# EzRing.net
KiCad netlist of a schematic drawn in Altium Designer
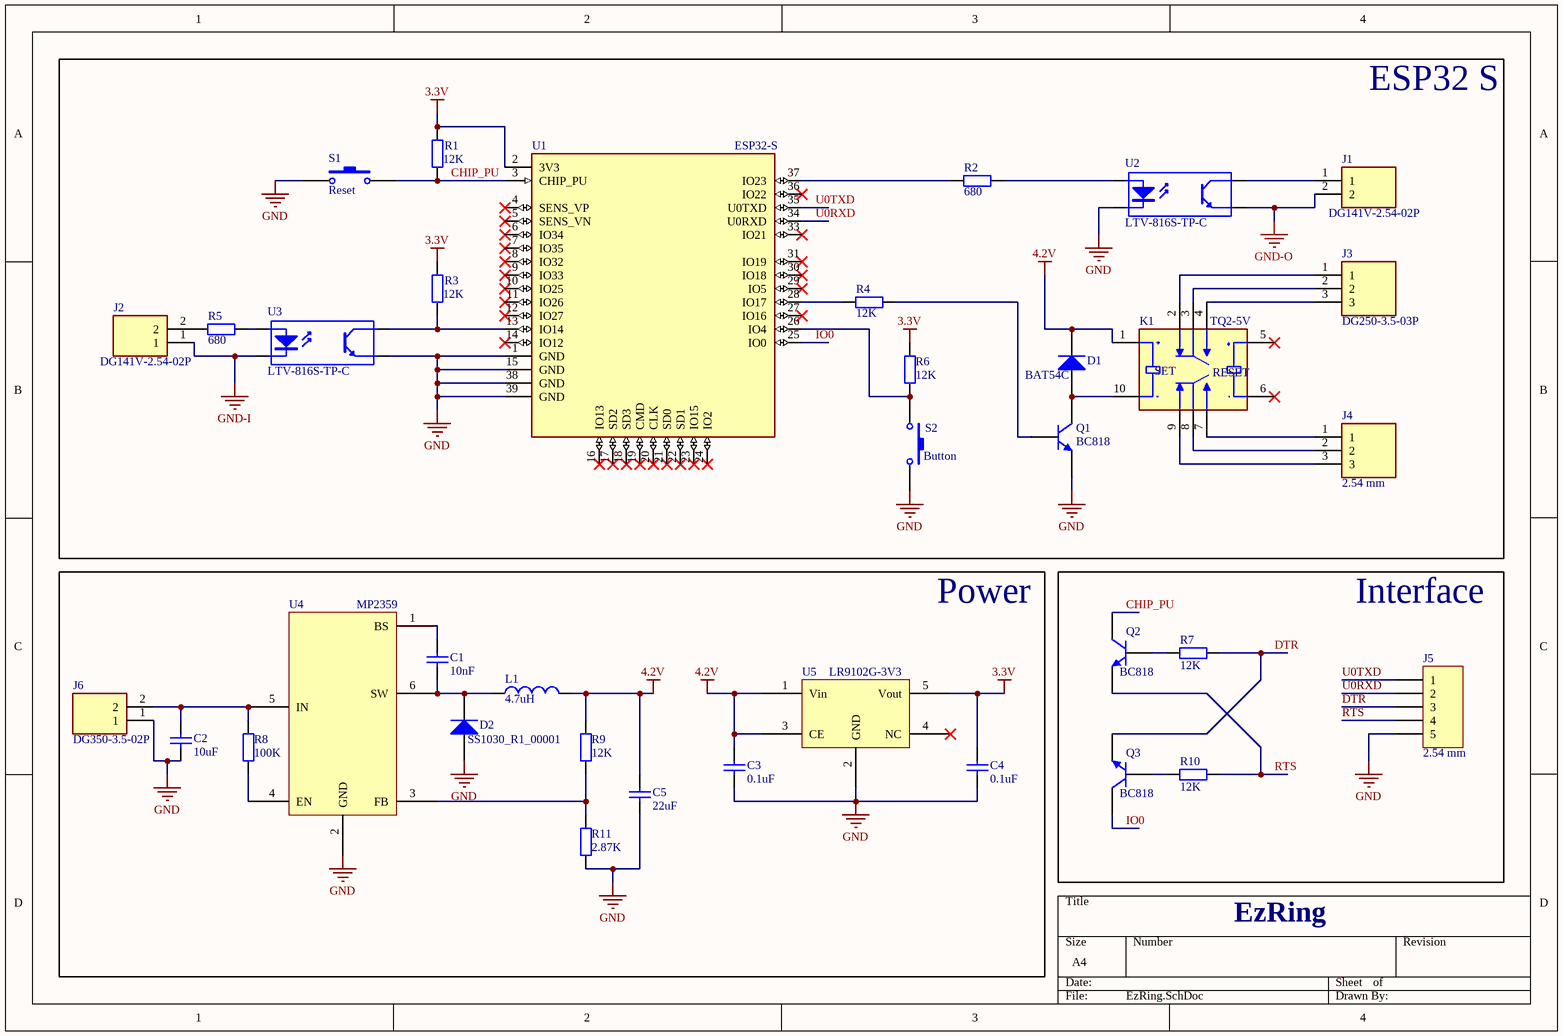
[diagram p0: EzRing.SchDoc]

(export (version "E")
  (design (tool "Eeschema 10.0.6"))
  (components
    (comp (ref "C1")
      (value "10nF")
      (footprint "0805")
      (description "MLCC (2012) 0805 10nF 100VDC ±10% X7R")
      (fields (field (name "OZDISAN PART#") "CL21B103KCANNNC") (field (name "PUBLISHER") "Altium Limited"))
      (libsource (lib "Miscellaneous Devices") (part "Cap"))
    )
    (comp (ref "C2")
      (value "10uF")
      (footprint "0805")
      (description "MLCC (2012) 0805 10uF 25VDC ±10% X5R")
      (fields (field (name "OZDISAN PART#") "CL21A106KAYNNNE") (field (name "PUBLISHER") "Altium Limited"))
      (libsource (lib "Miscellaneous Devices") (part "Cap"))
    )
    (comp (ref "C3")
      (value "0.1uF")
      (footprint "0805")
      (description "Capacitor")
      (fields (field (name "OZDISAN PART#") "CL21A226MAQNNNE") (field (name "PUBLISHER") "Altium Limited"))
      (libsource (lib "Miscellaneous Devices") (part "Cap"))
    )
    (comp (ref "C4")
      (value "0.1uF")
      (footprint "0805")
      (description "Capacitor")
      (fields (field (name "OZDISAN PART#") "CL21A226MAQNNNE") (field (name "PUBLISHER") "Altium Limited"))
      (libsource (lib "Miscellaneous Devices") (part "Cap"))
    )
    (comp (ref "C5")
      (value "22uF")
      (footprint "0805")
      (description "MLCC (2012) 0805 22uF 6.3VDC ±20% X5R")
      (fields (field (name "OZDISAN PART#") "CL21A226MQQNNNE") (field (name "PUBLISHER") "Altium Limited"))
      (libsource (lib "Miscellaneous Devices") (part "Cap"))
    )
    (comp (ref "D1")
      (value "BAT54C")
      (footprint "BAT54 series")
      (description "DIODE SCHOTTKY 2*0.2A 30V SOT23 CATHODE PHILIPS")
      (fields (field (name "OZDISAN PART#") "BAT54C,215") (field (name "PUBLISHER") "Altium Limited"))
      (libsource (lib "Miscellaneous Devices") (part "Diode"))
    )
    (comp (ref "D2")
      (value "SS1030_R1_00001")
      (footprint "SOD123 DIODE")
      (description "DIODE SCHOTTKY 1A 30V SOD123 SMT")
      (fields (field (name "PUBLISHER") "Altium Limited"))
      (libsource (lib "Miscellaneous Devices") (part "Diode"))
    )
    (comp (ref "J1")
      (value "DG141V-2.54-02P")
      (footprint "term blk 2p 2.54 2 leg 5.08 between legs")
      (fields
        (field (name "MP") "282843-2")
        (field (name "MF") "{'manufacturer': 'TE Connectivity'}")
        (field (name "OZDISAN PART#") "DG141V-2.54-02P-14-00AH")
      )
      (libsource (lib "MT-Sources") (part "282843-2"))
    )
    (comp (ref "J2")
      (value "DG141V-2.54-02P")
      (footprint "term blk 2p 2.54 2 leg 5.08 between legs")
      (fields
        (field (name "MP") "282843-2")
        (field (name "MF") "{'manufacturer': 'TE Connectivity'}")
        (field (name "OZDISAN PART#") "DG141V-2.54-02P-14-00AH")
      )
      (libsource (lib "") (part "282843-2_1"))
    )
    (comp (ref "J3")
      (value "DG250-3.5-03P")
      (footprint "term blk 2.54 3p 2 leg 5.08  between leg")
      (description "TERM.BLK.3.50MM 3P PCB TYPE GRAY GAOSONG")
      (fields (field (name "MF") "TE Connectivity") (field (name "DIGI-KEY_PART_NUMBER") "A98085-ND"))
      (libsource (lib "MT-Sources") (part "282843-3"))
    )
    (comp (ref "J4")
      (value "2.54 mm")
      (footprint "HEADER-2.54-03")
      (description "TERMI-BLOCK PCB HEADER 2.54")
      (fields (field (name "MF") "TE Connectivity") (field (name "DIGI-KEY_PART_NUMBER") "A98085-ND"))
      (libsource (lib "MT-Sources") (part "282843-3"))
    )
    (comp (ref "J5")
      (value "2.54 mm")
      (footprint "HEADER-2.54-5P")
      (description "Header, 5-Pin boşta kalacak.")
      (fields (field (name "PUBLISHER") "Altium Limited"))
      (libsource (lib "Miscellaneous Connectors") (part "Header 5"))
    )
    (comp (ref "J6")
      (value "DG350-3.5-02P")
      (footprint "Header-3.5-02")
      (description "TERM.BLK.3.81MM 2P PCB TYPE GREEN GAOSONG")
      (fields (field (name "MP") "282843-2") (field (name "MF") "{'manufacturer': 'TE Connectivity'}"))
      (libsource (lib "") (part "282843-2_1"))
    )
    (comp (ref "K1")
      (value "TQ2-5V")
      (footprint "RELAY_TQ2_2C_PAN")
      (description "RELAY 1A 5VDC TELECOM TYPE PANASONIC")
      (fields (field (name "MP") "EE2-3TNUH-L") (field (name "MF") "KEMET"))
      (libsource (lib "MT-Sources") (part "EE2-3TNUH-L"))
    )
    (comp (ref "L1")
      (value "4.7uH")
      (footprint "INDC2012X10N")
      (description "INDUCTOR FIXED 0805 4.7UH SMD")
      (fields (field (name "OZDISAN PART#") "CL2012C-4R7M-N") (field (name "PUBLISHER") "Altium Limited"))
      (libsource (lib "Miscellaneous Devices") (part "Inductor"))
    )
    (comp (ref "Q1")
      (value "BC818")
      (footprint "BC818")
      (description "BC818-16W,115 - TRANSISTOR DIS.500mA 25V NPN SOT323 GEN. SMT")
      (fields (field (name "OZDISAN PART#") "BC818-16W,115") (field (name "PUBLISHER") "Altium Limited"))
      (libsource (lib "Miscellaneous Devices") (part "NPN"))
    )
    (comp (ref "Q2")
      (value "BC818")
      (footprint "BC818")
      (description "BC818-16W,115 - TRANSISTOR DIS.500mA 25V NPN SOT323 GEN. SMT")
      (fields (field (name "OZDISAN PART#") "BC818-16W,115") (field (name "PUBLISHER") "Altium Limited"))
      (libsource (lib "Miscellaneous Devices") (part "NPN"))
    )
    (comp (ref "Q3")
      (value "BC818")
      (footprint "BC818")
      (description "BC818-16W,115 - TRANSISTOR DIS.500mA 25V NPN SOT323 GEN. SMT")
      (fields (field (name "OZDISAN PART#") "BC818-16W,115") (field (name "PUBLISHER") "Altium Limited"))
      (libsource (lib "Miscellaneous Devices") (part "NPN"))
    )
    (comp (ref "R1")
      (value "12K")
      (footprint "0805")
      (description "Resistor")
      (fields (field (name "OZDISAN PART#") "0805S8J0123T5E") (field (name "PUBLISHER") "Altium Limited"))
      (libsource (lib "") (part "Res2_2"))
    )
    (comp (ref "R2")
      (value "680")
      (footprint "0805")
      (description "Resistor")
      (fields (field (name "OZDISAN PART#") "0805S8J0681T5E") (field (name "PUBLISHER") "Altium Limited"))
      (libsource (lib "Miscellaneous Devices") (part "Res2"))
    )
    (comp (ref "R3")
      (value "12K")
      (footprint "0805")
      (description "Resistor")
      (fields (field (name "OZDISAN PART#") "0805S8J0123T5E") (field (name "PUBLISHER") "Altium Limited"))
      (libsource (lib "") (part "Res2_2"))
    )
    (comp (ref "R4")
      (value "12K")
      (footprint "0805")
      (description "Resistor")
      (fields (field (name "OZDISAN PART#") "0805S8J0123T5E") (field (name "PUBLISHER") "Altium Limited"))
      (libsource (lib "") (part "Res2_3"))
    )
    (comp (ref "R5")
      (value "680")
      (footprint "AXIAL-0.4")
      (description "Dip Resistor")
      (fields (field (name "OZDISAN PART#") "MF01WJJ0681A10") (field (name "PUBLISHER") "Altium Limited"))
      (libsource (lib "Miscellaneous Devices") (part "Res2"))
    )
    (comp (ref "R6")
      (value "12K")
      (footprint "0805")
      (description "Resistor")
      (fields (field (name "OZDISAN PART#") "0805S8J0123T5E") (field (name "PUBLISHER") "Altium Limited"))
      (libsource (lib "") (part "Res2_1"))
    )
    (comp (ref "R7")
      (value "12K")
      (footprint "0805")
      (description "Resistor")
      (fields (field (name "OZDISAN PART#") "0805S8J0123T5E") (field (name "PUBLISHER") "Altium Limited"))
      (libsource (lib "Miscellaneous Devices") (part "Res2"))
    )
    (comp (ref "R8")
      (value "100K")
      (footprint "0805")
      (description "Resistor")
      (fields (field (name "OZDISAN PART#") "0805S8J0104T5E") (field (name "PUBLISHER") "Altium Limited"))
      (libsource (lib "") (part "Res2_1"))
    )
    (comp (ref "R9")
      (value "12K")
      (footprint "0805")
      (description "Resistor")
      (fields (field (name "OZDISAN PART#") "0805S8J0123T5E") (field (name "PUBLISHER") "Altium Limited"))
      (libsource (lib "") (part "Res2_1"))
    )
    (comp (ref "R10")
      (value "12K")
      (footprint "0805")
      (description "Resistor")
      (fields (field (name "OZDISAN PART#") "0805S8J0123T5E") (field (name "PUBLISHER") "Altium Limited"))
      (libsource (lib "Miscellaneous Devices") (part "Res2"))
    )
    (comp (ref "R11")
      (value "2.87K")
      (footprint "0805")
      (description "Resistor")
      (fields (field (name "OZDISAN PART#") "0805S8F2871T5E") (field (name "PUBLISHER") "Altium Limited"))
      (libsource (lib "") (part "Res2_1"))
    )
    (comp (ref "S1")
      (value "Reset")
      (footprint "Kısa Devre anahtarlaması")
      (description "Burayı bir cımbız ile kısa devre yapılabilecek bir yapıda bırakacağız. buton koyulmayacak.")
      (fields (field (name "PUBLISHER") "Altium Limited"))
      (libsource (lib "Miscellaneous Devices") (part "SW-PB"))
    )
    (comp (ref "S2")
      (value "Button")
      (footprint "Push Button")
      (description "PUSH")
      (fields
        (field (name "OZDISAN PART#") "L-KLS7-TS6604-4.3-160-T")
        (field (name "PUBLISHER") "Altium Limited")
      )
      (libsource (lib "Miscellaneous Devices") (part "SW-PB"))
    )
    (comp (ref "U1")
      (value "ESP32-S")
      (footprint "ESP-32S")
      (fields (field (name "OZDISAN PART#") "ESP32-S (32MBIT)"))
      (libsource (lib "MT-Sources") (part "ESP32-S"))
    )
    (comp (ref "U2")
      (value "LTV-816S-TP-C")
      (footprint "OPTO LTV-816S")
      (description "IC-816 OPTO SMD")
      (fields (field (name "PUBLISHER") "Altium Limited"))
      (libsource (lib "Miscellaneous Devices") (part "Optoisolator1"))
    )
    (comp (ref "U3")
      (value "LTV-816S-TP-C")
      (footprint "OPTO LTV-816S")
      (description "IC-816 OPTO SMD")
      (fields (field (name "PUBLISHER") "Altium Limited"))
      (libsource (lib "Miscellaneous Devices") (part "Optoisolator1"))
    )
    (comp (ref "U4")
      (value "MP2359")
      (footprint "MP2359 vol reg TSOT23-6")
      (description "IC-2359 V.REG BUCK ADJ 1.2A TSOT23-6")
      (fields (field (name "OZDISAN PART#") "MP2359DJ-LF-Z"))
      (libsource (lib "MT-Sources") (part "MP2359"))
    )
    (comp (ref "U5")
      (value "LR9102G-3V3")
      (footprint "LR9102G-3V3-AE5-R")
      (description "IC-LR9102 V.REG 3V3 SOT-23-5 TR UTC (0-6,6V to 3,3V)")
      (fields (field (name "OZDISAN PART#") "LR9102G-3V3-AE5-R"))
      (libsource (lib "MT-Sources") (part "LR9102G-3V3"))
    )
  )
  (nets
    (net (code "1") (name "3.3V") (class "Default")
      (node (ref "C4") (pin "2") (pinfunction "2_2") (pintype "passive"))
      (node (ref "R1") (pin "1") (pinfunction "1_1") (pintype "passive"))
      (node (ref "R3") (pin "1") (pinfunction "1_1") (pintype "passive"))
      (node (ref "R6") (pin "2") (pinfunction "2_2") (pintype "passive"))
      (node (ref "U1") (pin "2") (pinfunction "3V3_2") (pintype "power_in"))
      (node (ref "U5") (pin "5") (pinfunction "Vout_5") (pintype "passive"))
    )
    (net (code "2") (name "4.2V") (class "Default")
      (node (ref "C3") (pin "2") (pinfunction "2_2") (pintype "passive"))
      (node (ref "C5") (pin "2") (pinfunction "2_2") (pintype "passive"))
      (node (ref "D1") (pin "2") (pinfunction "K_2") (pintype "passive"))
      (node (ref "K1") (pin "1") (pinfunction "1_1") (pintype "passive"))
      (node (ref "L1") (pin "2") (pinfunction "2_2") (pintype "passive"))
      (node (ref "R9") (pin "2") (pinfunction "2_2") (pintype "passive"))
      (node (ref "U5") (pin "1") (pinfunction "Vin_1") (pintype "passive"))
      (node (ref "U5") (pin "3") (pinfunction "CE_3") (pintype "passive"))
    )
    (net (code "3") (name "GND") (class "Default")
      (node (ref "C2") (pin "1") (pinfunction "1_1") (pintype "passive"))
      (node (ref "C3") (pin "1") (pinfunction "1_1") (pintype "passive"))
      (node (ref "C4") (pin "1") (pinfunction "1_1") (pintype "passive"))
      (node (ref "C5") (pin "1") (pinfunction "1_1") (pintype "passive"))
      (node (ref "D2") (pin "1") (pinfunction "A_1") (pintype "passive"))
      (node (ref "J5") (pin "5") (pinfunction "5_5") (pintype "passive"))
      (node (ref "J6") (pin "1") (pinfunction "1_1") (pintype "passive"))
      (node (ref "Q1") (pin "3") (pinfunction "E_3") (pintype "passive"))
      (node (ref "R11") (pin "1") (pinfunction "1_1") (pintype "passive"))
      (node (ref "S1") (pin "1") (pinfunction "1_1") (pintype "passive"))
      (node (ref "S2") (pin "2") (pinfunction "2_2") (pintype "passive"))
      (node (ref "U1") (pin "1") (pinfunction "GND_1") (pintype "power_in"))
      (node (ref "U1") (pin "15") (pinfunction "GND_15") (pintype "power_in"))
      (node (ref "U1") (pin "38") (pinfunction "GND_38") (pintype "power_in"))
      (node (ref "U1") (pin "39") (pinfunction "GND_39") (pintype "power_in"))
      (node (ref "U2") (pin "2") (pinfunction "K_2") (pintype "passive"))
      (node (ref "U3") (pin "3") (pinfunction "E_3") (pintype "passive"))
      (node (ref "U4") (pin "2") (pinfunction "GND_2") (pintype "passive"))
      (node (ref "U5") (pin "2") (pinfunction "GND_2") (pintype "passive"))
    )
    (net (code "4") (name "GND-I") (class "Default")
      (node (ref "J2") (pin "1") (pinfunction "1_1") (pintype "passive"))
      (node (ref "U3") (pin "2") (pinfunction "K_2") (pintype "passive"))
    )
    (net (code "5") (name "GND-O") (class "Default")
      (node (ref "J1") (pin "2") (pinfunction "2_2") (pintype "passive"))
      (node (ref "U2") (pin "3") (pinfunction "E_3") (pintype "passive"))
    )
    (net (code "6") (name "Net-(D1-A)") (class "Default")
      (node (ref "D1") (pin "1") (pinfunction "A_1") (pintype "passive"))
      (node (ref "K1") (pin "10") (pinfunction "10_10") (pintype "passive"))
      (node (ref "Q1") (pin "1") (pinfunction "C_1") (pintype "passive"))
    )
    (net (code "7") (name "Net-(D2-K)") (class "Default")
      (node (ref "C1") (pin "1") (pinfunction "1_1") (pintype "passive"))
      (node (ref "D2") (pin "2") (pinfunction "K_2") (pintype "passive"))
      (node (ref "L1") (pin "1") (pinfunction "1_1") (pintype "passive"))
      (node (ref "U4") (pin "6") (pinfunction "SW_6") (pintype "passive"))
    )
    (net (code "8") (name "Net-(J2-Pad2)") (class "Default")
      (node (ref "J2") (pin "2") (pinfunction "2_2") (pintype "passive"))
      (node (ref "R5") (pin "1") (pinfunction "1_1") (pintype "passive"))
    )
    (net (code "9") (name "Net-(J3-Pad1)") (class "Default")
      (node (ref "J3") (pin "1") (pinfunction "1_1") (pintype "passive"))
      (node (ref "K1") (pin "2") (pinfunction "2_2") (pintype "passive"))
    )
    (net (code "10") (name "Net-(J3-Pad2)") (class "Default")
      (node (ref "J3") (pin "2") (pinfunction "2_2") (pintype "passive"))
      (node (ref "K1") (pin "3") (pinfunction "3_3") (pintype "passive"))
    )
    (net (code "11") (name "Net-(J3-Pad3)") (class "Default")
      (node (ref "J3") (pin "3") (pinfunction "3_3") (pintype "passive"))
      (node (ref "K1") (pin "4") (pinfunction "4_4") (pintype "passive"))
    )
    (net (code "12") (name "Net-(J4-Pad1)") (class "Default")
      (node (ref "J4") (pin "1") (pinfunction "1_1") (pintype "passive"))
      (node (ref "K1") (pin "7") (pinfunction "7_7") (pintype "passive"))
    )
    (net (code "13") (name "Net-(J4-Pad2)") (class "Default")
      (node (ref "J4") (pin "2") (pinfunction "2_2") (pintype "passive"))
      (node (ref "K1") (pin "8") (pinfunction "8_8") (pintype "passive"))
    )
    (net (code "14") (name "Net-(J4-Pad3)") (class "Default")
      (node (ref "J4") (pin "3") (pinfunction "3_3") (pintype "passive"))
      (node (ref "K1") (pin "9") (pinfunction "9_9") (pintype "passive"))
    )
    (net (code "15") (name "Net-(Q1-B)") (class "Default")
      (node (ref "Q1") (pin "2") (pinfunction "B_2") (pintype "passive"))
      (node (ref "R4") (pin "1") (pinfunction "1_1") (pintype "passive"))
    )
    (net (code "16") (name "Net-(Q2-B)") (class "Default")
      (node (ref "Q2") (pin "2") (pinfunction "B_2") (pintype "passive"))
      (node (ref "R7") (pin "1") (pinfunction "1_1") (pintype "passive"))
    )
    (net (code "17") (name "Net-(Q2-E)") (class "Default")
      (node (ref "Q2") (pin "3") (pinfunction "E_3") (pintype "passive"))
      (node (ref "R10") (pin "2") (pinfunction "2_2") (pintype "passive"))
    )
    (net (code "18") (name "Net-(Q3-B)") (class "Default")
      (node (ref "Q3") (pin "2") (pinfunction "B_2") (pintype "passive"))
      (node (ref "R10") (pin "1") (pinfunction "1_1") (pintype "passive"))
    )
    (net (code "19") (name "Net-(Q3-E)") (class "Default")
      (node (ref "Q3") (pin "3") (pinfunction "E_3") (pintype "passive"))
      (node (ref "R7") (pin "2") (pinfunction "2_2") (pintype "passive"))
    )
    (net (code "20") (name "Net-(U1-CHIP_PU)") (class "Default")
      (node (ref "R1") (pin "2") (pinfunction "2_2") (pintype "passive"))
      (node (ref "S1") (pin "2") (pinfunction "2_2") (pintype "passive"))
      (node (ref "U1") (pin "3") (pinfunction "CHIP_PU_3") (pintype "input"))
    )
    (net (code "21") (name "Net-(U1-IO4)") (class "Default")
      (node (ref "R6") (pin "1") (pinfunction "1_1") (pintype "passive"))
      (node (ref "S2") (pin "1") (pinfunction "1_1") (pintype "passive"))
      (node (ref "U1") (pin "26") (pinfunction "IO4_26") (pintype "bidirectional"))
    )
    (net (code "22") (name "Net-(U1-IO14)") (class "Default")
      (node (ref "R3") (pin "2") (pinfunction "2_2") (pintype "passive"))
      (node (ref "U1") (pin "13") (pinfunction "IO14_13") (pintype "bidirectional"))
      (node (ref "U3") (pin "4") (pinfunction "C_4") (pintype "passive"))
    )
    (net (code "23") (name "Net-(U1-IO17)") (class "Default")
      (node (ref "R4") (pin "2") (pinfunction "2_2") (pintype "passive"))
      (node (ref "U1") (pin "28") (pinfunction "IO17_28") (pintype "bidirectional"))
    )
    (net (code "24") (name "Net-(U1-IO23)") (class "Default")
      (node (ref "R2") (pin "1") (pinfunction "1_1") (pintype "passive"))
      (node (ref "U1") (pin "37") (pinfunction "IO23_37") (pintype "bidirectional"))
    )
    (net (code "25") (name "Net-(U2-A)") (class "Default")
      (node (ref "R2") (pin "2") (pinfunction "2_2") (pintype "passive"))
      (node (ref "U2") (pin "1") (pinfunction "A_1") (pintype "passive"))
    )
    (net (code "26") (name "Net-(U2-C)") (class "Default")
      (node (ref "J1") (pin "1") (pinfunction "1_1") (pintype "passive"))
      (node (ref "U2") (pin "4") (pinfunction "C_4") (pintype "passive"))
    )
    (net (code "27") (name "Net-(U3-A)") (class "Default")
      (node (ref "R5") (pin "2") (pinfunction "2_2") (pintype "passive"))
      (node (ref "U3") (pin "1") (pinfunction "A_1") (pintype "passive"))
    )
    (net (code "28") (name "Net-(U4-BS)") (class "Default")
      (node (ref "C1") (pin "2") (pinfunction "2_2") (pintype "passive"))
      (node (ref "U4") (pin "1") (pinfunction "BS_1") (pintype "passive"))
    )
    (net (code "29") (name "Net-(U4-EN)") (class "Default")
      (node (ref "R8") (pin "1") (pinfunction "1_1") (pintype "passive"))
      (node (ref "U4") (pin "4") (pinfunction "EN_4") (pintype "passive"))
    )
    (net (code "30") (name "Net-(U4-FB)") (class "Default")
      (node (ref "R11") (pin "2") (pinfunction "2_2") (pintype "passive"))
      (node (ref "R9") (pin "1") (pinfunction "1_1") (pintype "passive"))
      (node (ref "U4") (pin "3") (pinfunction "FB_3") (pintype "passive"))
    )
    (net (code "31") (name "Net-(U4-IN)") (class "Default")
      (node (ref "C2") (pin "2") (pinfunction "2_2") (pintype "passive"))
      (node (ref "J6") (pin "2") (pinfunction "2_2") (pintype "passive"))
      (node (ref "R8") (pin "2") (pinfunction "2_2") (pintype "passive"))
      (node (ref "U4") (pin "5") (pinfunction "IN_5") (pintype "passive"))
    )
    (net (code "32") (name "unconnected-(J5-Pad1)") (class "Default")
      (node (ref "J5") (pin "1") (pinfunction "1_1") (pintype "passive"))
    )
    (net (code "33") (name "unconnected-(J5-Pad2)") (class "Default")
      (node (ref "J5") (pin "2") (pinfunction "2_2") (pintype "passive"))
    )
    (net (code "34") (name "unconnected-(J5-Pad3)") (class "Default")
      (node (ref "J5") (pin "3") (pinfunction "3_3") (pintype "passive"))
    )
    (net (code "35") (name "unconnected-(J5-Pad4)") (class "Default")
      (node (ref "J5") (pin "4") (pinfunction "4_4") (pintype "passive"))
    )
    (net (code "36") (name "unconnected-(K1-Pad5)") (class "Default")
      (node (ref "K1") (pin "5") (pinfunction "5_5") (pintype "passive+no_connect"))
    )
    (net (code "37") (name "unconnected-(K1-Pad6)") (class "Default")
      (node (ref "K1") (pin "6") (pinfunction "6_6") (pintype "passive+no_connect"))
    )
    (net (code "38") (name "unconnected-(Q2-C-Pad1)") (class "Default")
      (node (ref "Q2") (pin "1") (pinfunction "C_1") (pintype "passive"))
    )
    (net (code "39") (name "unconnected-(Q3-C-Pad1)") (class "Default")
      (node (ref "Q3") (pin "1") (pinfunction "C_1") (pintype "passive"))
    )
    (net (code "40") (name "unconnected-(U1-CLK-Pad20)") (class "Default")
      (node (ref "U1") (pin "20") (pinfunction "CLK_20") (pintype "bidirectional+no_connect"))
    )
    (net (code "41") (name "unconnected-(U1-CMD-Pad19)") (class "Default")
      (node (ref "U1") (pin "19") (pinfunction "CMD_19") (pintype "bidirectional+no_connect"))
    )
    (net (code "42") (name "unconnected-(U1-IO0-Pad25)") (class "Default")
      (node (ref "U1") (pin "25") (pinfunction "IO0_25") (pintype "bidirectional"))
    )
    (net (code "43") (name "unconnected-(U1-IO2-Pad24)") (class "Default")
      (node (ref "U1") (pin "24") (pinfunction "IO2_24") (pintype "bidirectional+no_connect"))
    )
    (net (code "44") (name "unconnected-(U1-IO5-Pad29)") (class "Default")
      (node (ref "U1") (pin "29") (pinfunction "IO5_29") (pintype "bidirectional+no_connect"))
    )
    (net (code "45") (name "unconnected-(U1-IO12-Pad14)") (class "Default")
      (node (ref "U1") (pin "14") (pinfunction "IO12_14") (pintype "bidirectional+no_connect"))
    )
    (net (code "46") (name "unconnected-(U1-IO13-Pad16)") (class "Default")
      (node (ref "U1") (pin "16") (pinfunction "IO13_16") (pintype "bidirectional+no_connect"))
    )
    (net (code "47") (name "unconnected-(U1-IO15-Pad23)") (class "Default")
      (node (ref "U1") (pin "23") (pinfunction "IO15_23") (pintype "bidirectional+no_connect"))
    )
    (net (code "48") (name "unconnected-(U1-IO16-Pad27)") (class "Default")
      (node (ref "U1") (pin "27") (pinfunction "IO16_27") (pintype "bidirectional+no_connect"))
    )
    (net (code "49") (name "unconnected-(U1-IO18-Pad30)") (class "Default")
      (node (ref "U1") (pin "30") (pinfunction "IO18_30") (pintype "bidirectional+no_connect"))
    )
    (net (code "50") (name "unconnected-(U1-IO19-Pad31)") (class "Default")
      (node (ref "U1") (pin "31") (pinfunction "IO19_31") (pintype "bidirectional+no_connect"))
    )
    (net (code "51") (name "unconnected-(U1-IO21-Pad33)") (class "Default")
      (node (ref "U1") (pin "33") (pinfunction "IO21_33") (pintype "bidirectional+no_connect"))
    )
    (net (code "52") (name "unconnected-(U1-IO22-Pad36)") (class "Default")
      (node (ref "U1") (pin "36") (pinfunction "IO22_36") (pintype "bidirectional+no_connect"))
    )
    (net (code "53") (name "unconnected-(U1-IO25-Pad10)") (class "Default")
      (node (ref "U1") (pin "10") (pinfunction "IO25_10") (pintype "bidirectional+no_connect"))
    )
    (net (code "54") (name "unconnected-(U1-IO26-Pad11)") (class "Default")
      (node (ref "U1") (pin "11") (pinfunction "IO26_11") (pintype "bidirectional+no_connect"))
    )
    (net (code "55") (name "unconnected-(U1-IO27-Pad12)") (class "Default")
      (node (ref "U1") (pin "12") (pinfunction "IO27_12") (pintype "bidirectional+no_connect"))
    )
    (net (code "56") (name "unconnected-(U1-IO32-Pad8)") (class "Default")
      (node (ref "U1") (pin "8") (pinfunction "IO32_8") (pintype "bidirectional+no_connect"))
    )
    (net (code "57") (name "unconnected-(U1-IO33-Pad9)") (class "Default")
      (node (ref "U1") (pin "9") (pinfunction "IO33_9") (pintype "bidirectional+no_connect"))
    )
    (net (code "58") (name "unconnected-(U1-IO34-Pad6)") (class "Default")
      (node (ref "U1") (pin "6") (pinfunction "IO34_6") (pintype "bidirectional+no_connect"))
    )
    (net (code "59") (name "unconnected-(U1-IO35-Pad7)") (class "Default")
      (node (ref "U1") (pin "7") (pinfunction "IO35_7") (pintype "bidirectional+no_connect"))
    )
    (net (code "60") (name "unconnected-(U1-SD0-Pad21)") (class "Default")
      (node (ref "U1") (pin "21") (pinfunction "SD0_21") (pintype "bidirectional+no_connect"))
    )
    (net (code "61") (name "unconnected-(U1-SD1-Pad22)") (class "Default")
      (node (ref "U1") (pin "22") (pinfunction "SD1_22") (pintype "bidirectional+no_connect"))
    )
    (net (code "62") (name "unconnected-(U1-SD2-Pad17)") (class "Default")
      (node (ref "U1") (pin "17") (pinfunction "SD2_17") (pintype "bidirectional+no_connect"))
    )
    (net (code "63") (name "unconnected-(U1-SD3-Pad18)") (class "Default")
      (node (ref "U1") (pin "18") (pinfunction "SD3_18") (pintype "bidirectional+no_connect"))
    )
    (net (code "64") (name "unconnected-(U1-SENS_VN-Pad5)") (class "Default")
      (node (ref "U1") (pin "5") (pinfunction "SENS_VN_5") (pintype "bidirectional+no_connect"))
    )
    (net (code "65") (name "unconnected-(U1-SENS_VP-Pad4)") (class "Default")
      (node (ref "U1") (pin "4") (pinfunction "SENS_VP_4") (pintype "bidirectional+no_connect"))
    )
    (net (code "66") (name "unconnected-(U1-U0RXD-Pad34)") (class "Default")
      (node (ref "U1") (pin "34") (pinfunction "U0RXD_34") (pintype "bidirectional"))
    )
    (net (code "67") (name "unconnected-(U1-U0TXD-Pad35)") (class "Default")
      (node (ref "U1") (pin "35") (pinfunction "U0TXD_35") (pintype "bidirectional"))
    )
    (net (code "68") (name "unconnected-(U5-NC-Pad4)") (class "Default")
      (node (ref "U5") (pin "4") (pinfunction "NC_4") (pintype "passive+no_connect"))
    )
  )
)
